# EFS_V2.net
KiCad netlist of a schematic drawn in EAGLE
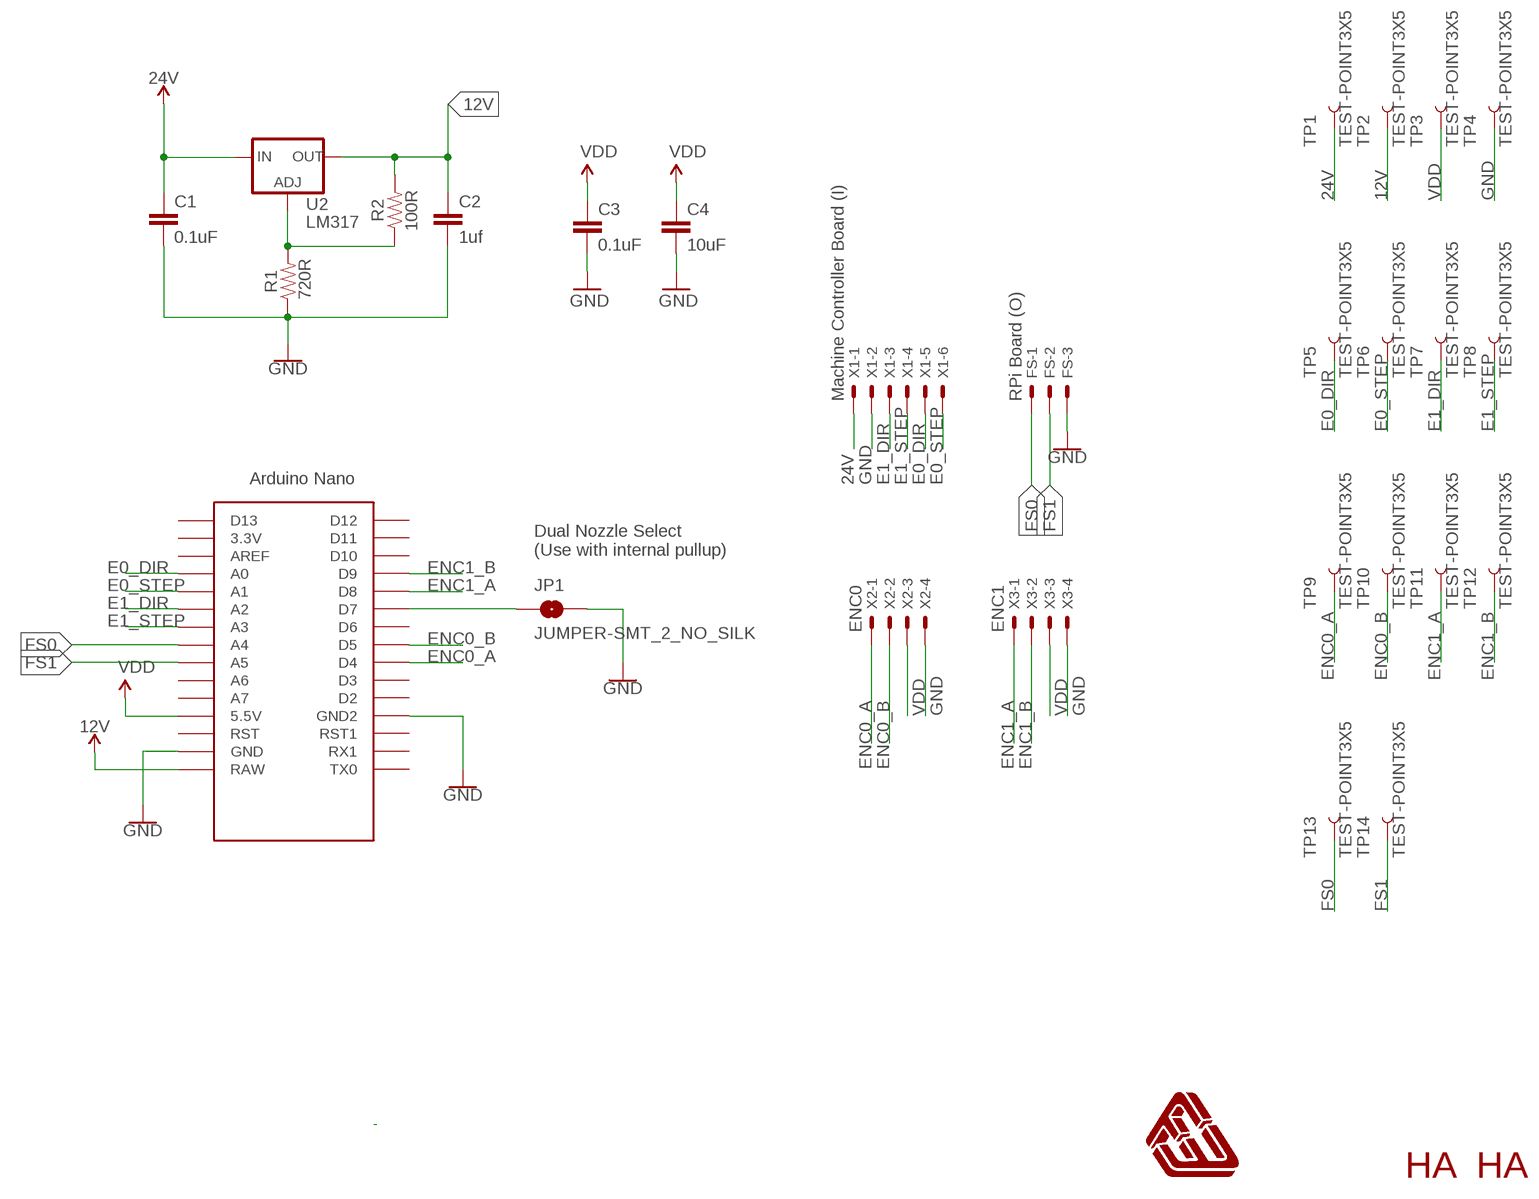
[diagram p0: schematic, sheet 1]

(export (version "E")
  (design (tool "Eeschema 10.0.6"))
  (components
    (comp (ref "C1")
      (value "0.1uF")
      (footprint "eagle-import:0603")
      (libsource (lib "eagle-import") (part "9.0PF-0603-50V-10%"))
    )
    (comp (ref "C2")
      (value "1uf")
      (footprint "eagle-import:0603")
      (libsource (lib "eagle-import") (part "9.0PF-0603-50V-10%"))
    )
    (comp (ref "C3")
      (value "0.1uF")
      (footprint "eagle-import:0603-CAP")
      (libsource (lib "eagle-import") (part "0.1UF-25V-5%(0603)"))
    )
    (comp (ref "C4")
      (value "10uF")
      (footprint "eagle-import:1210")
      (libsource (lib "eagle-import") (part "10UF50V20%(1210)"))
    )
    (comp (ref "FS")
      (value "RPi Board (O)")
      (footprint "eagle-import:JST-XH-03-PACKAGE-LONG-PAD")
      (libsource (lib "eagle-import") (part "JST-XH-03-PIN-LONG-PAD"))
    )
    (comp (ref "JP1")
      (value "JUMPER-SMT_2_NO_SILK")
      (footprint "eagle-import:SMT-JUMPER_2_NO_SILK")
      (libsource (lib "eagle-import") (part "JUMPER-SMT_2_NO_SILK"))
    )
    (comp (ref "M_HA_1")
      (value "HA_MARK")
      (footprint "eagle-import:HA_MARK")
      (libsource (lib "eagle-import") (part "HA_MARK"))
    )
    (comp (ref "M_HA_2")
      (value "HA_MARK")
      (footprint "eagle-import:HA_MARK")
      (libsource (lib "eagle-import") (part "HA_MARK"))
    )
    (comp (ref "R1")
      (value "720R")
      (footprint "eagle-import:0603")
      (libsource (lib "eagle-import") (part "RESISTOR0603"))
    )
    (comp (ref "R2")
      (value "100R")
      (footprint "eagle-import:0603")
      (libsource (lib "eagle-import") (part "RESISTOR0603"))
    )
    (comp (ref "TP1")
      (value "TEST-POINT3X5")
      (footprint "eagle-import:PAD.03X.05")
      (libsource (lib "eagle-import") (part "TEST-POINT3X5"))
    )
    (comp (ref "TP2")
      (value "TEST-POINT3X5")
      (footprint "eagle-import:PAD.03X.05")
      (libsource (lib "eagle-import") (part "TEST-POINT3X5"))
    )
    (comp (ref "TP3")
      (value "TEST-POINT3X5")
      (footprint "eagle-import:PAD.03X.05")
      (libsource (lib "eagle-import") (part "TEST-POINT3X5"))
    )
    (comp (ref "TP4")
      (value "TEST-POINT3X5")
      (footprint "eagle-import:PAD.03X.05")
      (libsource (lib "eagle-import") (part "TEST-POINT3X5"))
    )
    (comp (ref "TP5")
      (value "TEST-POINT3X5")
      (footprint "eagle-import:PAD.03X.05")
      (libsource (lib "eagle-import") (part "TEST-POINT3X5"))
    )
    (comp (ref "TP6")
      (value "TEST-POINT3X5")
      (footprint "eagle-import:PAD.03X.05")
      (libsource (lib "eagle-import") (part "TEST-POINT3X5"))
    )
    (comp (ref "TP7")
      (value "TEST-POINT3X5")
      (footprint "eagle-import:PAD.03X.05")
      (libsource (lib "eagle-import") (part "TEST-POINT3X5"))
    )
    (comp (ref "TP8")
      (value "TEST-POINT3X5")
      (footprint "eagle-import:PAD.03X.05")
      (libsource (lib "eagle-import") (part "TEST-POINT3X5"))
    )
    (comp (ref "TP9")
      (value "TEST-POINT3X5")
      (footprint "eagle-import:PAD.03X.05")
      (libsource (lib "eagle-import") (part "TEST-POINT3X5"))
    )
    (comp (ref "TP10")
      (value "TEST-POINT3X5")
      (footprint "eagle-import:PAD.03X.05")
      (libsource (lib "eagle-import") (part "TEST-POINT3X5"))
    )
    (comp (ref "TP11")
      (value "TEST-POINT3X5")
      (footprint "eagle-import:PAD.03X.05")
      (libsource (lib "eagle-import") (part "TEST-POINT3X5"))
    )
    (comp (ref "TP12")
      (value "TEST-POINT3X5")
      (footprint "eagle-import:PAD.03X.05")
      (libsource (lib "eagle-import") (part "TEST-POINT3X5"))
    )
    (comp (ref "TP13")
      (value "TEST-POINT3X5")
      (footprint "eagle-import:PAD.03X.05")
      (libsource (lib "eagle-import") (part "TEST-POINT3X5"))
    )
    (comp (ref "TP14")
      (value "TEST-POINT3X5")
      (footprint "eagle-import:PAD.03X.05")
      (libsource (lib "eagle-import") (part "TEST-POINT3X5"))
    )
    (comp (ref "U$1")
      (value "NANO")
      (footprint "eagle-import:NANO")
      (libsource (lib "eagle-import") (part "NANO"))
    )
    (comp (ref "U$2")
      (value "FWLOGO")
      (footprint "eagle-import:FWLOGO")
      (libsource (lib "eagle-import") (part "FWLOGO"))
    )
    (comp (ref "U2")
      (value "LM317")
      (footprint "eagle-import:SOT223")
      (libsource (lib "eagle-import") (part "V_REG_317SMD"))
    )
    (comp (ref "X1")
      (value "Machine Controller Board (I)")
      (footprint "eagle-import:JST-XH-06-PACKAGE-LONG-PAD")
      (libsource (lib "eagle-import") (part "JST-XH-06-PIN-LONG-PAD"))
    )
    (comp (ref "X2")
      (value "ENC0")
      (footprint "eagle-import:JST-XH-04-PACKAGE-LONG-PAD")
      (libsource (lib "eagle-import") (part "JST-XH-04-PIN-LONG-PAD"))
    )
    (comp (ref "X3")
      (value "ENC1")
      (footprint "eagle-import:JST-XH-04-PACKAGE-LONG-PAD")
      (libsource (lib "eagle-import") (part "JST-XH-04-PIN-LONG-PAD"))
    )
  )
  (nets
    (net (code "1") (name "/E0_DIR") (class "Default")
      (node (ref "TP5") (pin "P$1") (pinfunction "1_P$1") (pintype "bidirectional"))
      (node (ref "U$1") (pin "A0") (pinfunction "A0_A0") (pintype "bidirectional"))
      (node (ref "X1") (pin "5") (pinfunction "S_5") (pintype "passive"))
    )
    (net (code "2") (name "/E0_STEP") (class "Default")
      (node (ref "TP6") (pin "P$1") (pinfunction "1_P$1") (pintype "bidirectional"))
      (node (ref "U$1") (pin "A1") (pinfunction "A1_A1") (pintype "bidirectional"))
      (node (ref "X1") (pin "6") (pinfunction "S_6") (pintype "passive"))
    )
    (net (code "3") (name "/E1_DIR") (class "Default")
      (node (ref "TP7") (pin "P$1") (pinfunction "1_P$1") (pintype "bidirectional"))
      (node (ref "U$1") (pin "A2") (pinfunction "A2_A2") (pintype "bidirectional"))
      (node (ref "X1") (pin "3") (pinfunction "S_3") (pintype "passive"))
    )
    (net (code "4") (name "/E1_STEP") (class "Default")
      (node (ref "TP8") (pin "P$1") (pinfunction "1_P$1") (pintype "bidirectional"))
      (node (ref "U$1") (pin "A3") (pinfunction "A3_A3") (pintype "bidirectional"))
      (node (ref "X1") (pin "4") (pinfunction "S_4") (pintype "passive"))
    )
    (net (code "5") (name "/ENC0_A") (class "Default")
      (node (ref "TP9") (pin "P$1") (pinfunction "1_P$1") (pintype "bidirectional"))
      (node (ref "U$1") (pin "D4") (pinfunction "D4_D4") (pintype "bidirectional"))
      (node (ref "X2") (pin "1") (pinfunction "S_1") (pintype "passive"))
    )
    (net (code "6") (name "/ENC0_B") (class "Default")
      (node (ref "TP10") (pin "P$1") (pinfunction "1_P$1") (pintype "bidirectional"))
      (node (ref "U$1") (pin "D5") (pinfunction "D5_D5") (pintype "bidirectional"))
      (node (ref "X2") (pin "2") (pinfunction "S_2") (pintype "passive"))
    )
    (net (code "7") (name "/ENC1_A") (class "Default")
      (node (ref "TP11") (pin "P$1") (pinfunction "1_P$1") (pintype "bidirectional"))
      (node (ref "U$1") (pin "D8") (pinfunction "D8_D8") (pintype "bidirectional"))
      (node (ref "X3") (pin "1") (pinfunction "S_1") (pintype "passive"))
    )
    (net (code "8") (name "/ENC1_B") (class "Default")
      (node (ref "TP12") (pin "P$1") (pinfunction "1_P$1") (pintype "bidirectional"))
      (node (ref "U$1") (pin "D9") (pinfunction "D9_D9") (pintype "bidirectional"))
      (node (ref "X3") (pin "2") (pinfunction "S_2") (pintype "passive"))
    )
    (net (code "9") (name "12V") (class "Default")
      (node (ref "C2") (pin "1") (pinfunction "1_1") (pintype "passive"))
      (node (ref "R2") (pin "2") (pinfunction "2_2") (pintype "passive"))
      (node (ref "TP2") (pin "P$1") (pinfunction "1_P$1") (pintype "bidirectional"))
      (node (ref "U$1") (pin "RAW") (pinfunction "RAW_RAW") (pintype "bidirectional"))
      (node (ref "U2") (pin "2") (pinfunction "OUT_2") (pintype "output"))
    )
    (net (code "10") (name "24V") (class "Default")
      (node (ref "C1") (pin "1") (pinfunction "1_1") (pintype "passive"))
      (node (ref "TP1") (pin "P$1") (pinfunction "1_P$1") (pintype "bidirectional"))
      (node (ref "U2") (pin "3") (pinfunction "IN_3") (pintype "input"))
      (node (ref "X1") (pin "1") (pinfunction "S_1") (pintype "passive"))
    )
    (net (code "11") (name "FS0") (class "Default")
      (node (ref "FS") (pin "1") (pinfunction "S_1") (pintype "passive"))
      (node (ref "TP13") (pin "P$1") (pinfunction "1_P$1") (pintype "bidirectional"))
      (node (ref "U$1") (pin "A4") (pinfunction "A4_A4") (pintype "bidirectional"))
    )
    (net (code "12") (name "FS1") (class "Default")
      (node (ref "FS") (pin "2") (pinfunction "S_2") (pintype "passive"))
      (node (ref "TP14") (pin "P$1") (pinfunction "1_P$1") (pintype "bidirectional"))
      (node (ref "U$1") (pin "A5") (pinfunction "A5_A5") (pintype "bidirectional"))
    )
    (net (code "13") (name "GND") (class "Default")
      (node (ref "C1") (pin "2") (pinfunction "2_2") (pintype "passive"))
      (node (ref "C2") (pin "2") (pinfunction "2_2") (pintype "passive"))
      (node (ref "C3") (pin "2") (pinfunction "2_2") (pintype "passive"))
      (node (ref "C4") (pin "2") (pinfunction "2_2") (pintype "passive"))
      (node (ref "FS") (pin "3") (pinfunction "S_3") (pintype "passive"))
      (node (ref "JP1") (pin "2") (pinfunction "2_2") (pintype "passive"))
      (node (ref "R1") (pin "1") (pinfunction "1_1") (pintype "passive"))
      (node (ref "TP4") (pin "P$1") (pinfunction "1_P$1") (pintype "bidirectional"))
      (node (ref "U$1") (pin "GND") (pinfunction "GND_GND") (pintype "bidirectional"))
      (node (ref "U$1") (pin "GND1") (pinfunction "GND2_GND1") (pintype "bidirectional"))
      (node (ref "X1") (pin "2") (pinfunction "S_2") (pintype "passive"))
      (node (ref "X2") (pin "4") (pinfunction "S_4") (pintype "passive"))
      (node (ref "X3") (pin "4") (pinfunction "S_4") (pintype "passive"))
    )
    (net (code "14") (name "Net-(JP1-Pad1)") (class "Default")
      (node (ref "JP1") (pin "1") (pinfunction "1_1") (pintype "passive"))
      (node (ref "U$1") (pin "D7") (pinfunction "D7_D7") (pintype "bidirectional"))
    )
    (net (code "15") (name "Net-(U2-ADJ)") (class "Default")
      (node (ref "R1") (pin "2") (pinfunction "2_2") (pintype "passive"))
      (node (ref "R2") (pin "1") (pinfunction "1_1") (pintype "passive"))
      (node (ref "U2") (pin "1") (pinfunction "ADJ_1") (pintype "input"))
    )
    (net (code "16") (name "VDD") (class "Default")
      (node (ref "C3") (pin "1") (pinfunction "1_1") (pintype "passive"))
      (node (ref "C4") (pin "1") (pinfunction "1_1") (pintype "passive"))
      (node (ref "TP3") (pin "P$1") (pinfunction "1_P$1") (pintype "bidirectional"))
      (node (ref "U$1") (pin "5V") (pinfunction "5.5V_5V") (pintype "bidirectional"))
      (node (ref "X2") (pin "3") (pinfunction "S_3") (pintype "passive"))
      (node (ref "X3") (pin "3") (pinfunction "S_3") (pintype "passive"))
    )
    (net (code "17") (name "unconnected-(U$1-Pad3.3V)") (class "Default")
      (node (ref "U$1") (pin "3.3V") (pinfunction "3.3V_3.3V") (pintype "bidirectional"))
    )
    (net (code "18") (name "unconnected-(U$1-PadA6)") (class "Default")
      (node (ref "U$1") (pin "A6") (pinfunction "A6_A6") (pintype "bidirectional"))
    )
    (net (code "19") (name "unconnected-(U$1-PadA7)") (class "Default")
      (node (ref "U$1") (pin "A7") (pinfunction "A7_A7") (pintype "bidirectional"))
    )
    (net (code "20") (name "unconnected-(U$1-PadAREF)") (class "Default")
      (node (ref "U$1") (pin "AREF") (pinfunction "AREF_AREF") (pintype "bidirectional"))
    )
    (net (code "21") (name "unconnected-(U$1-PadD2)") (class "Default")
      (node (ref "U$1") (pin "D2") (pinfunction "D2_D2") (pintype "bidirectional"))
    )
    (net (code "22") (name "unconnected-(U$1-PadD3)") (class "Default")
      (node (ref "U$1") (pin "D3") (pinfunction "D3_D3") (pintype "bidirectional"))
    )
    (net (code "23") (name "unconnected-(U$1-PadD6)") (class "Default")
      (node (ref "U$1") (pin "D6") (pinfunction "D6_D6") (pintype "bidirectional"))
    )
    (net (code "24") (name "unconnected-(U$1-PadD10)") (class "Default")
      (node (ref "U$1") (pin "D10") (pinfunction "D10_D10") (pintype "bidirectional"))
    )
    (net (code "25") (name "unconnected-(U$1-PadD11)") (class "Default")
      (node (ref "U$1") (pin "D11") (pinfunction "D11_D11") (pintype "bidirectional"))
    )
    (net (code "26") (name "unconnected-(U$1-PadD12)") (class "Default")
      (node (ref "U$1") (pin "D12") (pinfunction "D12_D12") (pintype "bidirectional"))
    )
    (net (code "27") (name "unconnected-(U$1-PadD13)") (class "Default")
      (node (ref "U$1") (pin "D13") (pinfunction "D13_D13") (pintype "bidirectional"))
    )
    (net (code "28") (name "unconnected-(U$1-PadICSP1)") (class "Default")
      (node (ref "U$1") (pin "ICSP1") (pinfunction "ICSP1_ICSP1") (pintype "bidirectional"))
    )
    (net (code "29") (name "unconnected-(U$1-PadICSP2)") (class "Default")
      (node (ref "U$1") (pin "ICSP2") (pinfunction "ICSP2_ICSP2") (pintype "bidirectional"))
    )
    (net (code "30") (name "unconnected-(U$1-PadICSP3)") (class "Default")
      (node (ref "U$1") (pin "ICSP3") (pinfunction "ICSP3_ICSP3") (pintype "bidirectional"))
    )
    (net (code "31") (name "unconnected-(U$1-PadICSP4)") (class "Default")
      (node (ref "U$1") (pin "ICSP4") (pinfunction "ICSP4_ICSP4") (pintype "bidirectional"))
    )
    (net (code "32") (name "unconnected-(U$1-PadICSP5)") (class "Default")
      (node (ref "U$1") (pin "ICSP5") (pinfunction "ICSP5_ICSP5") (pintype "bidirectional"))
    )
    (net (code "33") (name "unconnected-(U$1-PadICSP6)") (class "Default")
      (node (ref "U$1") (pin "ICSP6") (pinfunction "ICSP6_ICSP6") (pintype "bidirectional"))
    )
    (net (code "34") (name "unconnected-(U$1-PadRST)") (class "Default")
      (node (ref "U$1") (pin "RST") (pinfunction "RST_RST") (pintype "bidirectional"))
    )
    (net (code "35") (name "unconnected-(U$1-PadRST1)") (class "Default")
      (node (ref "U$1") (pin "RST1") (pinfunction "RST1_RST1") (pintype "bidirectional"))
    )
    (net (code "36") (name "unconnected-(U$1-PadRX1)") (class "Default")
      (node (ref "U$1") (pin "RX1") (pinfunction "RX1_RX1") (pintype "bidirectional"))
    )
    (net (code "37") (name "unconnected-(U$1-PadTX0)") (class "Default")
      (node (ref "U$1") (pin "TX0") (pinfunction "TX0_TX0") (pintype "bidirectional"))
    )
  )
)
